# input_amp_v1_1.net
KiCad netlist of a schematic drawn in EAGLE
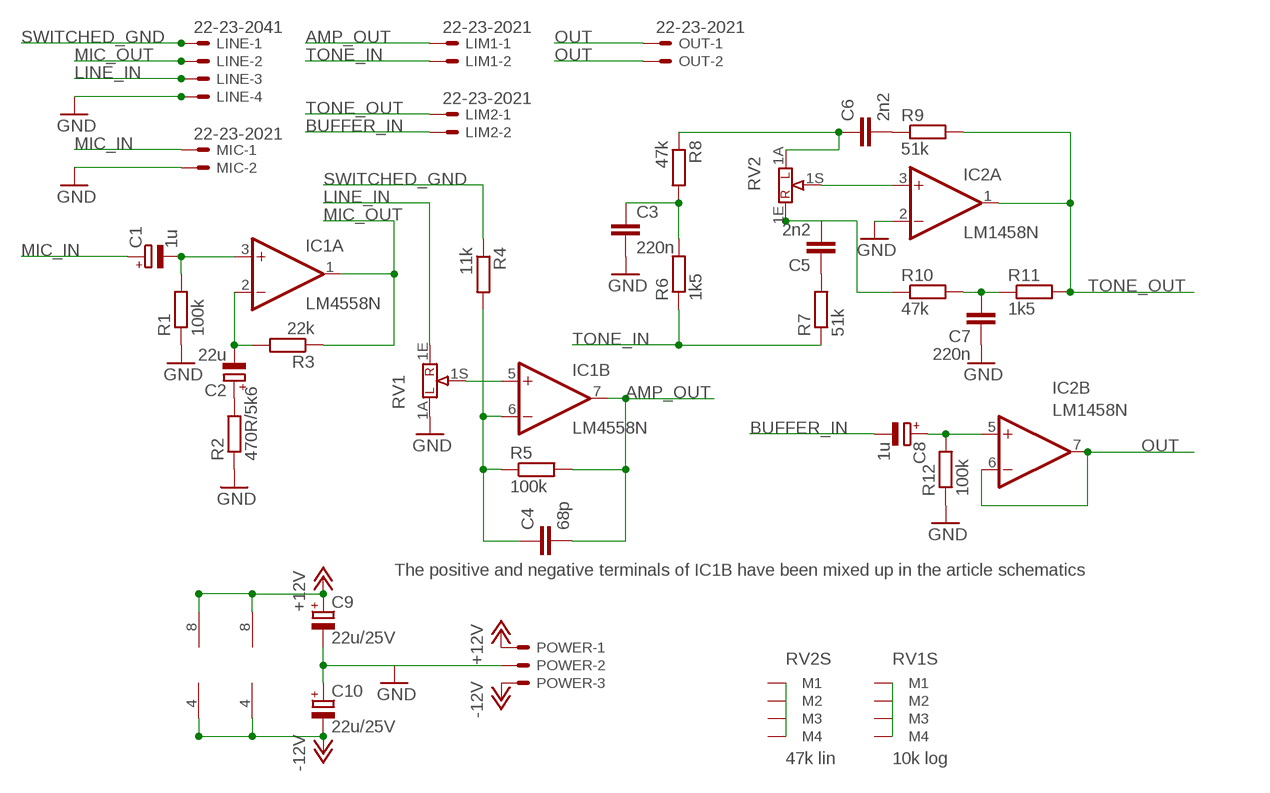
[diagram p0: schematic, sheet 1]

(export (version "E")
  (design (tool "Eeschema 10.0.6"))
  (components
    (comp (ref "C1")
      (value "1u")
      (footprint "eagle-import:E2,5-5")
      (libsource (lib "eagle-import") (part "CPOL-EUE2.5-5"))
    )
    (comp (ref "C2")
      (value "22u")
      (footprint "eagle-import:E2,5-5")
      (libsource (lib "eagle-import") (part "CPOL-EUE2.5-5"))
    )
    (comp (ref "C3")
      (value "220n")
      (footprint "eagle-import:C050-030X075")
      (libsource (lib "eagle-import") (part "C-EU050-030X075"))
    )
    (comp (ref "C4")
      (value "68p")
      (footprint "eagle-import:C025-025X050")
      (libsource (lib "eagle-import") (part "C-EU025-025X050"))
    )
    (comp (ref "C5")
      (value "2n2")
      (footprint "eagle-import:C050-030X075")
      (libsource (lib "eagle-import") (part "C-EU050-030X075"))
    )
    (comp (ref "C6")
      (value "2n2")
      (footprint "eagle-import:C050-030X075")
      (libsource (lib "eagle-import") (part "C-EU050-030X075"))
    )
    (comp (ref "C7")
      (value "220n")
      (footprint "eagle-import:C050-030X075")
      (libsource (lib "eagle-import") (part "C-EU050-030X075"))
    )
    (comp (ref "C8")
      (value "1u")
      (footprint "eagle-import:E2,5-5")
      (libsource (lib "eagle-import") (part "CPOL-EUE2.5-5"))
    )
    (comp (ref "C9")
      (value "22u/25V")
      (footprint "eagle-import:E2,5-5")
      (libsource (lib "eagle-import") (part "CPOL-EUE2.5-5"))
    )
    (comp (ref "C10")
      (value "22u/25V")
      (footprint "eagle-import:E2,5-5")
      (libsource (lib "eagle-import") (part "CPOL-EUE2.5-5"))
    )
    (comp (ref "IC1")
      (value "LM4558N")
      (footprint "eagle-import:DIL08")
      (libsource (lib "eagle-import") (part "4558NLM"))
    )
    (comp (ref "IC2")
      (value "LM1458N")
      (footprint "eagle-import:DIL08")
      (libsource (lib "eagle-import") (part "1458NLM"))
    )
    (comp (ref "LIM1")
      (value "22-23-2021")
      (footprint "eagle-import:22-23-2021")
      (fields (field (name "MF") "MOLEX"))
      (libsource (lib "eagle-import") (part "22-23-2021"))
    )
    (comp (ref "LIM2")
      (value "22-23-2021")
      (footprint "eagle-import:22-23-2021")
      (fields (field (name "MF") "MOLEX"))
      (libsource (lib "eagle-import") (part "22-23-2021"))
    )
    (comp (ref "LINE")
      (value "22-23-2041")
      (footprint "eagle-import:22-23-2041")
      (fields (field (name "MF") "MOLEX"))
      (libsource (lib "eagle-import") (part "22-23-2041"))
    )
    (comp (ref "MIC")
      (value "22-23-2021")
      (footprint "eagle-import:22-23-2021")
      (fields (field (name "MF") "MOLEX"))
      (libsource (lib "eagle-import") (part "22-23-2021"))
    )
    (comp (ref "OUT")
      (value "22-23-2021")
      (footprint "eagle-import:22-23-2021")
      (fields (field (name "MF") "MOLEX"))
      (libsource (lib "eagle-import") (part "22-23-2021"))
    )
    (comp (ref "POWER")
      (value "KK-156-3")
      (footprint "eagle-import:KK-156-3")
      (libsource (lib "eagle-import") (part "KK-156-3"))
    )
    (comp (ref "R1")
      (value "100k")
      (footprint "eagle-import:0207_7")
      (libsource (lib "eagle-import") (part "R-EU_0207/7"))
    )
    (comp (ref "R2")
      (value "470R/5k6")
      (footprint "eagle-import:0207_7")
      (libsource (lib "eagle-import") (part "R-EU_0207/7"))
    )
    (comp (ref "R3")
      (value "22k")
      (footprint "eagle-import:0207_7")
      (libsource (lib "eagle-import") (part "R-EU_0207/7"))
    )
    (comp (ref "R4")
      (value "11k")
      (footprint "eagle-import:0207_7")
      (libsource (lib "eagle-import") (part "R-EU_0207/7"))
    )
    (comp (ref "R5")
      (value "100k")
      (footprint "eagle-import:0207_7")
      (libsource (lib "eagle-import") (part "R-EU_0207/7"))
    )
    (comp (ref "R6")
      (value "1k5")
      (footprint "eagle-import:0207_7")
      (libsource (lib "eagle-import") (part "R-EU_0207/7"))
    )
    (comp (ref "R7")
      (value "51k")
      (footprint "eagle-import:0207_7")
      (libsource (lib "eagle-import") (part "R-EU_0207/7"))
    )
    (comp (ref "R8")
      (value "47k")
      (footprint "eagle-import:0207_7")
      (libsource (lib "eagle-import") (part "R-EU_0207/7"))
    )
    (comp (ref "R9")
      (value "51k")
      (footprint "eagle-import:0207_7")
      (libsource (lib "eagle-import") (part "R-EU_0207/7"))
    )
    (comp (ref "R10")
      (value "47k")
      (footprint "eagle-import:0207_7")
      (libsource (lib "eagle-import") (part "R-EU_0207/7"))
    )
    (comp (ref "R11")
      (value "1k5")
      (footprint "eagle-import:0207_7")
      (libsource (lib "eagle-import") (part "R-EU_0207/7"))
    )
    (comp (ref "R12")
      (value "100k")
      (footprint "eagle-import:0207_7")
      (libsource (lib "eagle-import") (part "R-EU_0207/7"))
    )
    (comp (ref "RV1")
      (value "10k log")
      (footprint "eagle-import:POT16_W_BRACKET")
      (libsource (lib "eagle-import") (part "POT16_W_BRACKET{dblquote}{dblquote}"))
    )
    (comp (ref "RV2")
      (value "47k lin")
      (footprint "eagle-import:POT16_W_BRACKET")
      (libsource (lib "eagle-import") (part "POT16_W_BRACKET{dblquote}{dblquote}"))
    )
  )
  (nets
    (net (code "1") (name "+12V") (class "Default")
      (node (ref "C9") (pin "+") (pinfunction "+_+") (pintype "passive"))
      (node (ref "IC1") (pin "8") (pinfunction "V+_8") (pintype "power_in"))
      (node (ref "IC2") (pin "8") (pinfunction "V+_8") (pintype "power_in"))
      (node (ref "POWER") (pin "1") (pinfunction "S_1") (pintype "passive"))
    )
    (net (code "2") (name "-12V") (class "Default")
      (node (ref "C10") (pin "-") (pinfunction "-_-") (pintype "passive"))
      (node (ref "IC1") (pin "4") (pinfunction "V-_4") (pintype "power_in"))
      (node (ref "IC2") (pin "4") (pinfunction "V-_4") (pintype "power_in"))
      (node (ref "POWER") (pin "3") (pinfunction "S_3") (pintype "passive"))
    )
    (net (code "3") (name "/AMP_OUT") (class "Default")
      (node (ref "C4") (pin "2") (pinfunction "2_2") (pintype "passive"))
      (node (ref "IC1") (pin "7") (pinfunction "OUT_7") (pintype "output"))
      (node (ref "LIM1") (pin "1") (pinfunction "S_1") (pintype "passive"))
      (node (ref "R5") (pin "2") (pinfunction "2_2") (pintype "passive"))
    )
    (net (code "4") (name "/BUFFER_IN") (class "Default")
      (node (ref "C8") (pin "-") (pinfunction "-_-") (pintype "passive"))
      (node (ref "LIM2") (pin "2") (pinfunction "S_2") (pintype "passive"))
    )
    (net (code "5") (name "/LINE_IN") (class "Default")
      (node (ref "LINE") (pin "3") (pinfunction "S_3") (pintype "passive"))
      (node (ref "RV1") (pin "1E") (pinfunction "1E_1E") (pintype "passive"))
    )
    (net (code "6") (name "/MIC_IN") (class "Default")
      (node (ref "C1") (pin "+") (pinfunction "+_+") (pintype "passive"))
      (node (ref "MIC") (pin "1") (pinfunction "S_1") (pintype "passive"))
    )
    (net (code "7") (name "/MIC_OUT") (class "Default")
      (node (ref "IC1") (pin "1") (pinfunction "OUT_1") (pintype "output"))
      (node (ref "LINE") (pin "2") (pinfunction "S_2") (pintype "passive"))
      (node (ref "R3") (pin "1") (pinfunction "1_1") (pintype "passive"))
    )
    (net (code "8") (name "/OUT") (class "Default")
      (node (ref "IC2") (pin "6") (pinfunction "-IN_6") (pintype "input"))
      (node (ref "IC2") (pin "7") (pinfunction "OUT_7") (pintype "output"))
      (node (ref "OUT") (pin "1") (pinfunction "S_1") (pintype "passive"))
      (node (ref "OUT") (pin "2") (pinfunction "S_2") (pintype "passive"))
    )
    (net (code "9") (name "/SWITCHED_GND") (class "Default")
      (node (ref "LINE") (pin "1") (pinfunction "S_1") (pintype "passive"))
      (node (ref "R4") (pin "1") (pinfunction "1_1") (pintype "passive"))
    )
    (net (code "10") (name "/TONE_IN") (class "Default")
      (node (ref "LIM1") (pin "2") (pinfunction "S_2") (pintype "passive"))
      (node (ref "R6") (pin "1") (pinfunction "1_1") (pintype "passive"))
      (node (ref "R7") (pin "1") (pinfunction "1_1") (pintype "passive"))
    )
    (net (code "11") (name "/TONE_OUT") (class "Default")
      (node (ref "IC2") (pin "1") (pinfunction "OUT_1") (pintype "output"))
      (node (ref "LIM2") (pin "1") (pinfunction "S_1") (pintype "passive"))
      (node (ref "R11") (pin "2") (pinfunction "2_2") (pintype "passive"))
      (node (ref "R9") (pin "2") (pinfunction "2_2") (pintype "passive"))
    )
    (net (code "12") (name "GND") (class "Default")
      (node (ref "C10") (pin "+") (pinfunction "+_+") (pintype "passive"))
      (node (ref "C3") (pin "2") (pinfunction "2_2") (pintype "passive"))
      (node (ref "C7") (pin "1") (pinfunction "1_1") (pintype "passive"))
      (node (ref "C9") (pin "-") (pinfunction "-_-") (pintype "passive"))
      (node (ref "IC2") (pin "2") (pinfunction "-IN_2") (pintype "input"))
      (node (ref "LINE") (pin "4") (pinfunction "S_4") (pintype "passive"))
      (node (ref "MIC") (pin "2") (pinfunction "S_2") (pintype "passive"))
      (node (ref "POWER") (pin "2") (pinfunction "S_2") (pintype "passive"))
      (node (ref "R1") (pin "1") (pinfunction "1_1") (pintype "passive"))
      (node (ref "R12") (pin "1") (pinfunction "1_1") (pintype "passive"))
      (node (ref "R2") (pin "1") (pinfunction "1_1") (pintype "passive"))
      (node (ref "RV1") (pin "1A") (pinfunction "1A_1A") (pintype "passive"))
    )
    (net (code "13") (name "Net-(C2-Pad+)") (class "Default")
      (node (ref "C2") (pin "+") (pinfunction "+_+") (pintype "passive"))
      (node (ref "R2") (pin "2") (pinfunction "2_2") (pintype "passive"))
    )
    (net (code "14") (name "Net-(C3-Pad1)") (class "Default")
      (node (ref "C3") (pin "1") (pinfunction "1_1") (pintype "passive"))
      (node (ref "R6") (pin "2") (pinfunction "2_2") (pintype "passive"))
      (node (ref "R8") (pin "2") (pinfunction "2_2") (pintype "passive"))
    )
    (net (code "15") (name "Net-(C5-Pad1)") (class "Default")
      (node (ref "C5") (pin "1") (pinfunction "1_1") (pintype "passive"))
      (node (ref "R7") (pin "2") (pinfunction "2_2") (pintype "passive"))
    )
    (net (code "16") (name "Net-(C5-Pad2)") (class "Default")
      (node (ref "C5") (pin "2") (pinfunction "2_2") (pintype "passive"))
      (node (ref "R10") (pin "1") (pinfunction "1_1") (pintype "passive"))
      (node (ref "RV2") (pin "1E") (pinfunction "1E_1E") (pintype "passive"))
    )
    (net (code "17") (name "Net-(C6-Pad1)") (class "Default")
      (node (ref "C6") (pin "1") (pinfunction "1_1") (pintype "passive"))
      (node (ref "R8") (pin "1") (pinfunction "1_1") (pintype "passive"))
      (node (ref "RV2") (pin "1A") (pinfunction "1A_1A") (pintype "passive"))
    )
    (net (code "18") (name "Net-(C6-Pad2)") (class "Default")
      (node (ref "C6") (pin "2") (pinfunction "2_2") (pintype "passive"))
      (node (ref "R9") (pin "1") (pinfunction "1_1") (pintype "passive"))
    )
    (net (code "19") (name "Net-(C7-Pad2)") (class "Default")
      (node (ref "C7") (pin "2") (pinfunction "2_2") (pintype "passive"))
      (node (ref "R10") (pin "2") (pinfunction "2_2") (pintype "passive"))
      (node (ref "R11") (pin "1") (pinfunction "1_1") (pintype "passive"))
    )
    (net (code "20") (name "Net-(IC1A-+IN)") (class "Default")
      (node (ref "C1") (pin "-") (pinfunction "-_-") (pintype "passive"))
      (node (ref "IC1") (pin "3") (pinfunction "+IN_3") (pintype "input"))
      (node (ref "R1") (pin "2") (pinfunction "2_2") (pintype "passive"))
    )
    (net (code "21") (name "Net-(IC1A--IN)") (class "Default")
      (node (ref "C2") (pin "-") (pinfunction "-_-") (pintype "passive"))
      (node (ref "IC1") (pin "2") (pinfunction "-IN_2") (pintype "input"))
      (node (ref "R3") (pin "2") (pinfunction "2_2") (pintype "passive"))
    )
    (net (code "22") (name "Net-(IC1B-+IN)") (class "Default")
      (node (ref "IC1") (pin "5") (pinfunction "+IN_5") (pintype "input"))
      (node (ref "RV1") (pin "1S") (pinfunction "1S_1S") (pintype "passive"))
    )
    (net (code "23") (name "Net-(IC1B--IN)") (class "Default")
      (node (ref "C4") (pin "1") (pinfunction "1_1") (pintype "passive"))
      (node (ref "IC1") (pin "6") (pinfunction "-IN_6") (pintype "input"))
      (node (ref "R4") (pin "2") (pinfunction "2_2") (pintype "passive"))
      (node (ref "R5") (pin "1") (pinfunction "1_1") (pintype "passive"))
    )
    (net (code "24") (name "Net-(IC2A-+IN)") (class "Default")
      (node (ref "IC2") (pin "3") (pinfunction "+IN_3") (pintype "input"))
      (node (ref "RV2") (pin "1S") (pinfunction "1S_1S") (pintype "passive"))
    )
    (net (code "25") (name "Net-(IC2B-+IN)") (class "Default")
      (node (ref "C8") (pin "+") (pinfunction "+_+") (pintype "passive"))
      (node (ref "IC2") (pin "5") (pinfunction "+IN_5") (pintype "input"))
      (node (ref "R12") (pin "2") (pinfunction "2_2") (pintype "passive"))
    )
    (net (code "26") (name "unconnected-(RV1-PadM1)") (class "Default")
      (node (ref "RV1") (pin "M1") (pinfunction "M1_M1") (pintype "passive"))
    )
    (net (code "27") (name "unconnected-(RV1-PadM2)") (class "Default")
      (node (ref "RV1") (pin "M2") (pinfunction "M2_M2") (pintype "passive"))
    )
    (net (code "28") (name "unconnected-(RV1-PadM3)") (class "Default")
      (node (ref "RV1") (pin "M3") (pinfunction "M3_M3") (pintype "passive"))
    )
    (net (code "29") (name "unconnected-(RV1-PadM4)") (class "Default")
      (node (ref "RV1") (pin "M4") (pinfunction "M4_M4") (pintype "passive"))
    )
    (net (code "30") (name "unconnected-(RV2-PadM1)") (class "Default")
      (node (ref "RV2") (pin "M1") (pinfunction "M1_M1") (pintype "passive"))
    )
    (net (code "31") (name "unconnected-(RV2-PadM2)") (class "Default")
      (node (ref "RV2") (pin "M2") (pinfunction "M2_M2") (pintype "passive"))
    )
    (net (code "32") (name "unconnected-(RV2-PadM3)") (class "Default")
      (node (ref "RV2") (pin "M3") (pinfunction "M3_M3") (pintype "passive"))
    )
    (net (code "33") (name "unconnected-(RV2-PadM4)") (class "Default")
      (node (ref "RV2") (pin "M4") (pinfunction "M4_M4") (pintype "passive"))
    )
  )
)
